# control_driver.net
KiCad netlist of a schematic drawn in EAGLE
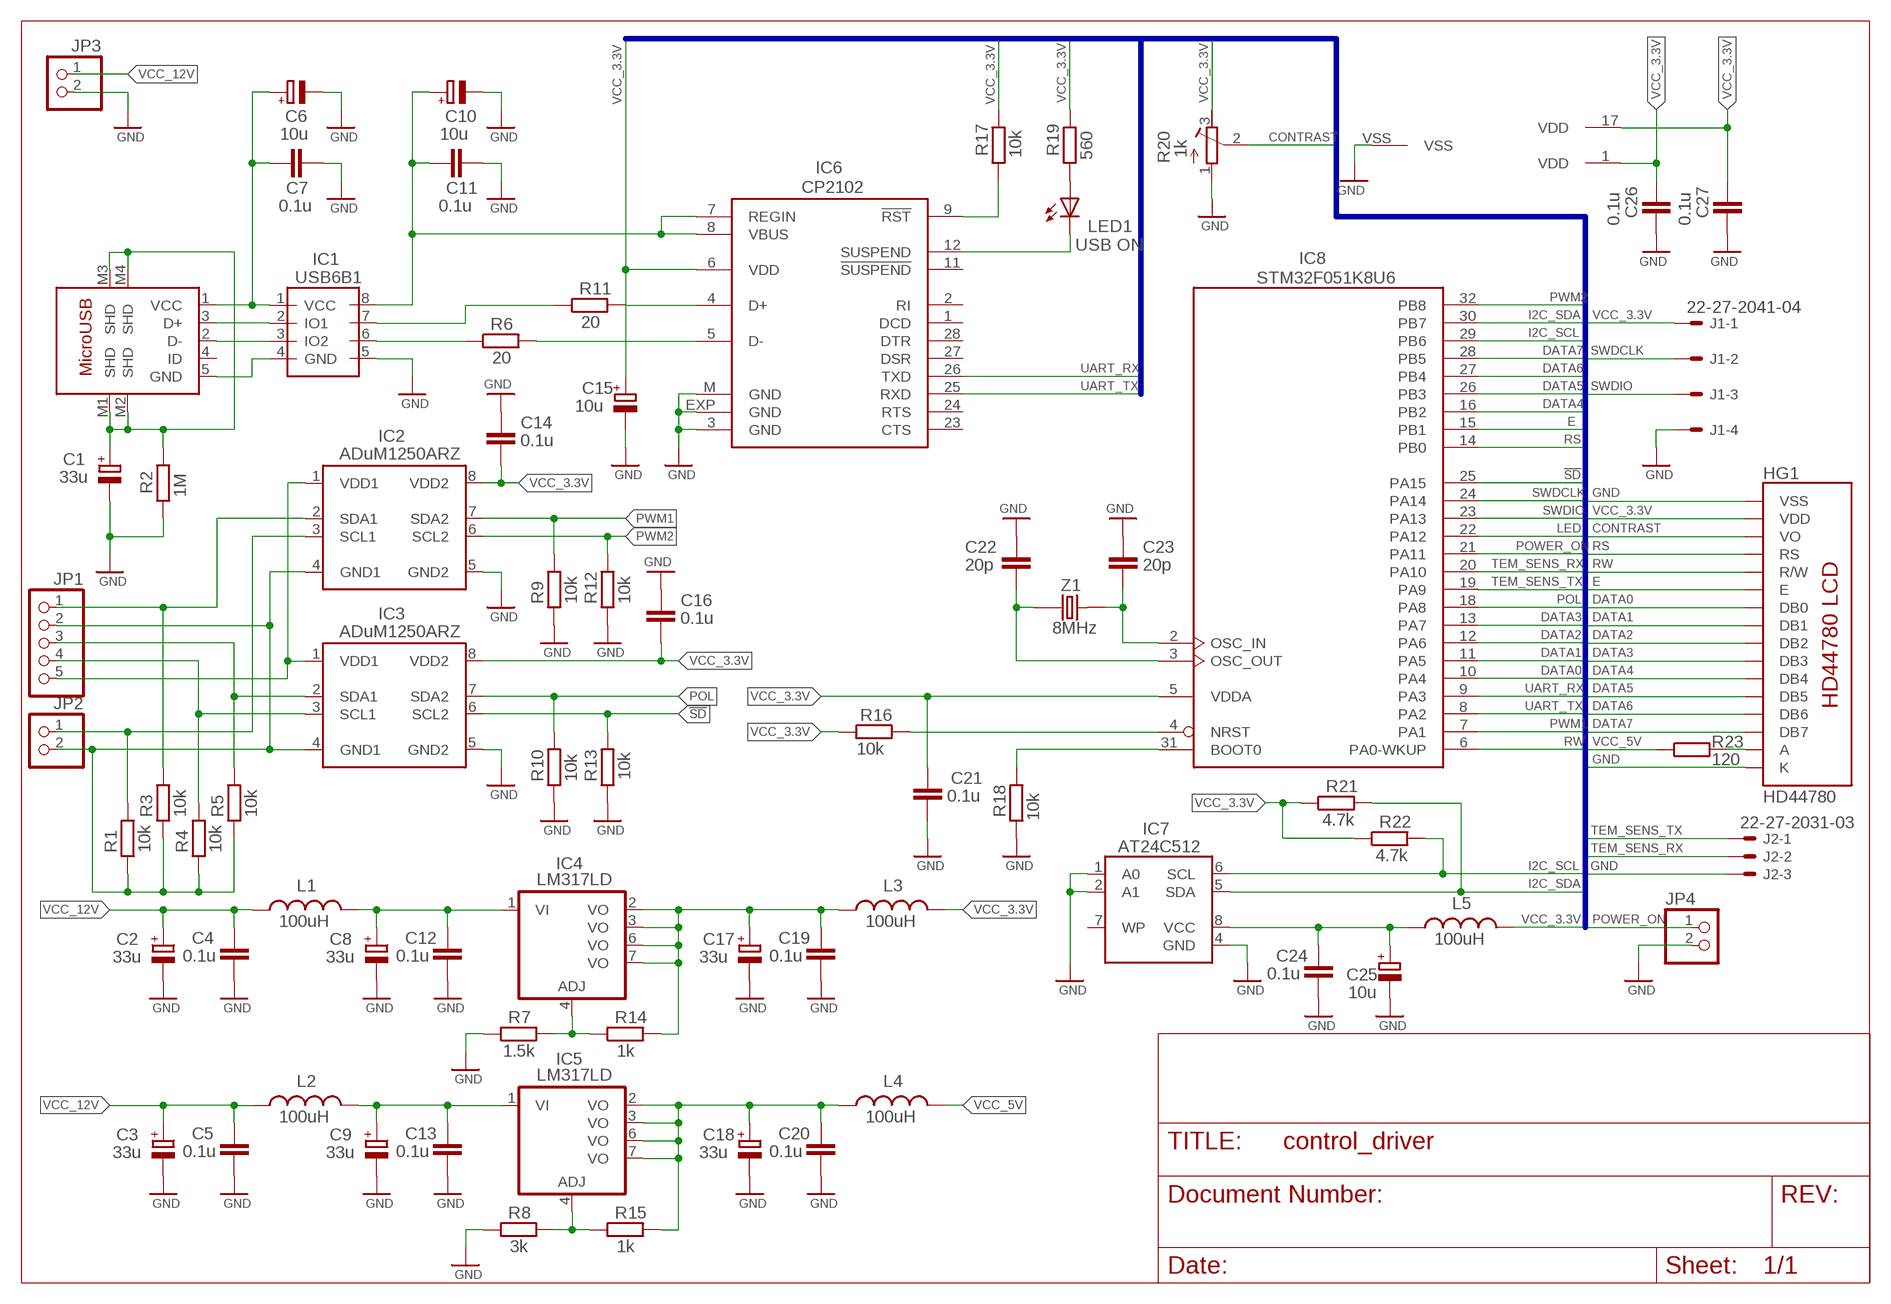
[diagram p0: schematic, sheet 1]

(export (version "E")
  (design (tool "Eeschema 10.0.6"))
  (components
    (comp (ref "C1")
      (value "33u")
      (footprint "eagle-import:SMC_B")
      (libsource (lib "eagle-import") (part "CPOL-EUSMCB"))
    )
    (comp (ref "C2")
      (value "33u")
      (footprint "eagle-import:SMC_C")
      (libsource (lib "eagle-import") (part "CPOL-EUSMCC"))
    )
    (comp (ref "C3")
      (value "33u")
      (footprint "eagle-import:SMC_C")
      (libsource (lib "eagle-import") (part "CPOL-EUSMCC"))
    )
    (comp (ref "C4")
      (value "0.1u")
      (footprint "eagle-import:C0603")
      (libsource (lib "eagle-import") (part "C-EUC0603"))
    )
    (comp (ref "C5")
      (value "0.1u")
      (footprint "eagle-import:C0603")
      (libsource (lib "eagle-import") (part "C-EUC0603"))
    )
    (comp (ref "C6")
      (value "10u")
      (footprint "eagle-import:SMC_A")
      (libsource (lib "eagle-import") (part "CPOL-EUSMCA"))
    )
    (comp (ref "C7")
      (value "0.1u")
      (footprint "eagle-import:C0603")
      (libsource (lib "eagle-import") (part "C-EUC0603"))
    )
    (comp (ref "C8")
      (value "33u")
      (footprint "eagle-import:SMC_C")
      (libsource (lib "eagle-import") (part "CPOL-EUSMCC"))
    )
    (comp (ref "C9")
      (value "33u")
      (footprint "eagle-import:SMC_C")
      (libsource (lib "eagle-import") (part "CPOL-EUSMCC"))
    )
    (comp (ref "C10")
      (value "10u")
      (footprint "eagle-import:SMC_A")
      (libsource (lib "eagle-import") (part "CPOL-EUSMCA"))
    )
    (comp (ref "C11")
      (value "0.1u")
      (footprint "eagle-import:C0603")
      (libsource (lib "eagle-import") (part "C-EUC0603"))
    )
    (comp (ref "C12")
      (value "0.1u")
      (footprint "eagle-import:C0603")
      (libsource (lib "eagle-import") (part "C-EUC0603"))
    )
    (comp (ref "C13")
      (value "0.1u")
      (footprint "eagle-import:C0603")
      (libsource (lib "eagle-import") (part "C-EUC0603"))
    )
    (comp (ref "C14")
      (value "0.1u")
      (footprint "eagle-import:C0603")
      (libsource (lib "eagle-import") (part "C-EUC0603"))
    )
    (comp (ref "C15")
      (value "10u")
      (footprint "eagle-import:SMC_A")
      (libsource (lib "eagle-import") (part "CPOL-EUSMCA"))
    )
    (comp (ref "C16")
      (value "0.1u")
      (footprint "eagle-import:C0603")
      (libsource (lib "eagle-import") (part "C-EUC0603"))
    )
    (comp (ref "C17")
      (value "33u")
      (footprint "eagle-import:SMC_B")
      (libsource (lib "eagle-import") (part "CPOL-EUSMCB"))
    )
    (comp (ref "C18")
      (value "33u")
      (footprint "eagle-import:SMC_B")
      (libsource (lib "eagle-import") (part "CPOL-EUSMCB"))
    )
    (comp (ref "C19")
      (value "0.1u")
      (footprint "eagle-import:C0603")
      (libsource (lib "eagle-import") (part "C-EUC0603"))
    )
    (comp (ref "C20")
      (value "0.1u")
      (footprint "eagle-import:C0603")
      (libsource (lib "eagle-import") (part "C-EUC0603"))
    )
    (comp (ref "C21")
      (value "0.1u")
      (footprint "eagle-import:C0603")
      (libsource (lib "eagle-import") (part "C-EUC0603"))
    )
    (comp (ref "C22")
      (value "20p")
      (footprint "eagle-import:C0603")
      (libsource (lib "eagle-import") (part "C-EUC0603"))
    )
    (comp (ref "C23")
      (value "20p")
      (footprint "eagle-import:C0603")
      (libsource (lib "eagle-import") (part "C-EUC0603"))
    )
    (comp (ref "C24")
      (value "0.1u")
      (footprint "eagle-import:C0603")
      (libsource (lib "eagle-import") (part "C-EUC0603"))
    )
    (comp (ref "C25")
      (value "10u")
      (footprint "eagle-import:SMC_A")
      (libsource (lib "eagle-import") (part "CPOL-EUSMCA"))
    )
    (comp (ref "C26")
      (value "0.1u")
      (footprint "eagle-import:C0603")
      (libsource (lib "eagle-import") (part "C-EUC0603"))
    )
    (comp (ref "C27")
      (value "0.1u")
      (footprint "eagle-import:C0603")
      (libsource (lib "eagle-import") (part "C-EUC0603"))
    )
    (comp (ref "HG1")
      (value "HD44780")
      (footprint "eagle-import:LCD-16X2-4HOLES")
      (libsource (lib "eagle-import") (part "LCD-HD4478016X2-4-HOLES4-HOLES"))
    )
    (comp (ref "IC1")
      (value "USB6B1")
      (footprint "eagle-import:SO08")
      (libsource (lib "eagle-import") (part "USB6B1"))
    )
    (comp (ref "IC2")
      (value "ADuM1250ARZ")
      (footprint "eagle-import:SO8")
      (libsource (lib "eagle-import") (part "ADUM1250"))
    )
    (comp (ref "IC3")
      (value "ADuM1250ARZ")
      (footprint "eagle-import:SO8")
      (libsource (lib "eagle-import") (part "ADUM1250"))
    )
    (comp (ref "IC4")
      (value "LM317LD")
      (footprint "eagle-import:SO08")
      (libsource (lib "eagle-import") (part "LM317LD"))
    )
    (comp (ref "IC5")
      (value "LM317LD")
      (footprint "eagle-import:SO08")
      (libsource (lib "eagle-import") (part "LM317LD"))
    )
    (comp (ref "IC6")
      (value "CP2102")
      (footprint "eagle-import:MLP28")
      (fields (field (name "MF") "FARNELL") (field (name "MPN") "CP2102-GM"))
      (libsource (lib "eagle-import") (part "CP2102"))
    )
    (comp (ref "IC7")
      (value "AT24C512")
      (footprint "eagle-import:SO8")
      (libsource (lib "eagle-import") (part "24C512"))
    )
    (comp (ref "IC8")
      (value "STM32F051K8U6")
      (footprint "eagle-import:UFQFPN32")
      (libsource (lib "eagle-import") (part "STM32F051KU8"))
    )
    (comp (ref "J1")
      (value "22-27-2041-04")
      (footprint "eagle-import:6410-04")
      (libsource (lib "eagle-import") (part "22-?-0427-2041"))
    )
    (comp (ref "J2")
      (value "22-27-2031-03")
      (footprint "eagle-import:6410-03")
      (libsource (lib "eagle-import") (part "22-?-0327-2031"))
    )
    (comp (ref "JP1")
      (value "PINHD-1X55X2MM")
      (footprint "eagle-import:1_05X2MM")
      (libsource (lib "eagle-import") (part "PINHD-1X55X2MM"))
    )
    (comp (ref "JP2")
      (value "PINHD-1X2")
      (footprint "eagle-import:1X02")
      (libsource (lib "eagle-import") (part "PINHD-1X2"))
    )
    (comp (ref "JP3")
      (value "PINHD-1X2")
      (footprint "eagle-import:1X02")
      (libsource (lib "eagle-import") (part "PINHD-1X2"))
    )
    (comp (ref "JP4")
      (value "PINHD-1X2")
      (footprint "eagle-import:1X02")
      (libsource (lib "eagle-import") (part "PINHD-1X2"))
    )
    (comp (ref "L1")
      (value "100uH")
      (footprint "eagle-import:C0603")
      (libsource (lib "eagle-import") (part "L-US"))
    )
    (comp (ref "L2")
      (value "100uH")
      (footprint "eagle-import:C0603")
      (libsource (lib "eagle-import") (part "L-US"))
    )
    (comp (ref "L3")
      (value "100uH")
      (footprint "eagle-import:C0603")
      (libsource (lib "eagle-import") (part "L-US"))
    )
    (comp (ref "L4")
      (value "100uH")
      (footprint "eagle-import:C0603")
      (libsource (lib "eagle-import") (part "L-US"))
    )
    (comp (ref "L5")
      (value "100uH")
      (footprint "eagle-import:C0603")
      (libsource (lib "eagle-import") (part "L-US"))
    )
    (comp (ref "LED1")
      (value "USB ON")
      (footprint "eagle-import:CHIPLED_0805")
      (libsource (lib "eagle-import") (part "LEDCHIPLED_0805"))
    )
    (comp (ref "R1")
      (value "10k")
      (footprint "eagle-import:R0603")
      (libsource (lib "eagle-import") (part "R-EU_R0603"))
    )
    (comp (ref "R2")
      (value "1M")
      (footprint "eagle-import:R0603")
      (libsource (lib "eagle-import") (part "R-EU_R0603"))
    )
    (comp (ref "R3")
      (value "10k")
      (footprint "eagle-import:R0603")
      (libsource (lib "eagle-import") (part "R-EU_R0603"))
    )
    (comp (ref "R4")
      (value "10k")
      (footprint "eagle-import:R0603")
      (libsource (lib "eagle-import") (part "R-EU_R0603"))
    )
    (comp (ref "R5")
      (value "10k")
      (footprint "eagle-import:R0603")
      (libsource (lib "eagle-import") (part "R-EU_R0603"))
    )
    (comp (ref "R6")
      (value "20")
      (footprint "eagle-import:R0603")
      (libsource (lib "eagle-import") (part "R-EU_R0603"))
    )
    (comp (ref "R7")
      (value "1.5k")
      (footprint "eagle-import:R0603")
      (libsource (lib "eagle-import") (part "R-EU_R0603"))
    )
    (comp (ref "R8")
      (value "3k")
      (footprint "eagle-import:R0603")
      (libsource (lib "eagle-import") (part "R-EU_R0603"))
    )
    (comp (ref "R9")
      (value "10k")
      (footprint "eagle-import:R0603")
      (libsource (lib "eagle-import") (part "R-EU_R0603"))
    )
    (comp (ref "R10")
      (value "10k")
      (footprint "eagle-import:R0603")
      (libsource (lib "eagle-import") (part "R-EU_R0603"))
    )
    (comp (ref "R11")
      (value "20")
      (footprint "eagle-import:R0603")
      (libsource (lib "eagle-import") (part "R-EU_R0603"))
    )
    (comp (ref "R12")
      (value "10k")
      (footprint "eagle-import:R0603")
      (libsource (lib "eagle-import") (part "R-EU_R0603"))
    )
    (comp (ref "R13")
      (value "10k")
      (footprint "eagle-import:R0603")
      (libsource (lib "eagle-import") (part "R-EU_R0603"))
    )
    (comp (ref "R14")
      (value "1k")
      (footprint "eagle-import:R0603")
      (libsource (lib "eagle-import") (part "R-EU_R0603"))
    )
    (comp (ref "R15")
      (value "1k")
      (footprint "eagle-import:R0603")
      (libsource (lib "eagle-import") (part "R-EU_R0603"))
    )
    (comp (ref "R16")
      (value "10k")
      (footprint "eagle-import:R0603")
      (libsource (lib "eagle-import") (part "R-EU_R0603"))
    )
    (comp (ref "R17")
      (value "10k")
      (footprint "eagle-import:R0603")
      (libsource (lib "eagle-import") (part "R-EU_R0603"))
    )
    (comp (ref "R18")
      (value "10k")
      (footprint "eagle-import:R0603")
      (libsource (lib "eagle-import") (part "R-EU_R0603"))
    )
    (comp (ref "R19")
      (value "560")
      (footprint "eagle-import:R0603")
      (libsource (lib "eagle-import") (part "R-EU_R0603"))
    )
    (comp (ref "R20")
      (value "1k")
      (footprint "eagle-import:RTRIM4G_J")
      (libsource (lib "eagle-import") (part "R-TRIMM4G/J"))
    )
    (comp (ref "R21")
      (value "4.7k")
      (footprint "eagle-import:R0603")
      (libsource (lib "eagle-import") (part "R-EU_R0603"))
    )
    (comp (ref "R22")
      (value "4.7k")
      (footprint "eagle-import:R0603")
      (libsource (lib "eagle-import") (part "R-EU_R0603"))
    )
    (comp (ref "R23")
      (value "120")
      (footprint "eagle-import:R0805")
      (libsource (lib "eagle-import") (part "R-EU_R0805"))
    )
    (comp (ref "X1")
      (value "MICRO-USB")
      (footprint "eagle-import:ZX62R-B-5P")
      (libsource (lib "eagle-import") (part "MICRO-USB"))
    )
    (comp (ref "Z1")
      (value "8MHz")
      (footprint "eagle-import:CRYSTAL_5X7")
      (libsource (lib "eagle-import") (part "CRYSTAL_5X7MM"))
    )
  )
  (nets
    (net (code "1") (name "/CONTRAST") (class "Default")
      (node (ref "HG1") (pin "3") (pinfunction "VO_3") (pintype "bidirectional"))
      (node (ref "R20") (pin "2") (pinfunction "S_2") (pintype "passive"))
    )
    (net (code "2") (name "/DATA0") (class "Default")
      (node (ref "HG1") (pin "7") (pinfunction "DB0_7") (pintype "bidirectional"))
      (node (ref "IC8") (pin "10") (pinfunction "PA4_10") (pintype "bidirectional"))
    )
    (net (code "3") (name "/DATA1") (class "Default")
      (node (ref "HG1") (pin "8") (pinfunction "DB1_8") (pintype "bidirectional"))
      (node (ref "IC8") (pin "11") (pinfunction "PA5_11") (pintype "bidirectional"))
    )
    (net (code "4") (name "/DATA2") (class "Default")
      (node (ref "HG1") (pin "9") (pinfunction "DB2_9") (pintype "bidirectional"))
      (node (ref "IC8") (pin "12") (pinfunction "PA6_12") (pintype "bidirectional"))
    )
    (net (code "5") (name "/DATA3") (class "Default")
      (node (ref "HG1") (pin "10") (pinfunction "DB3_10") (pintype "bidirectional"))
      (node (ref "IC8") (pin "13") (pinfunction "PA7_13") (pintype "bidirectional"))
    )
    (net (code "6") (name "/DATA4") (class "Default")
      (node (ref "HG1") (pin "11") (pinfunction "DB4_11") (pintype "bidirectional"))
      (node (ref "IC8") (pin "16") (pinfunction "PB2_16") (pintype "bidirectional"))
    )
    (net (code "7") (name "/DATA5") (class "Default")
      (node (ref "HG1") (pin "12") (pinfunction "DB5_12") (pintype "bidirectional"))
      (node (ref "IC8") (pin "26") (pinfunction "PB3_26") (pintype "bidirectional"))
    )
    (net (code "8") (name "/DATA6") (class "Default")
      (node (ref "HG1") (pin "13") (pinfunction "DB6_13") (pintype "bidirectional"))
      (node (ref "IC8") (pin "27") (pinfunction "PB4_27") (pintype "bidirectional"))
    )
    (net (code "9") (name "/DATA7") (class "Default")
      (node (ref "HG1") (pin "14") (pinfunction "DB7_14") (pintype "bidirectional"))
      (node (ref "IC8") (pin "28") (pinfunction "PB5_28") (pintype "bidirectional"))
    )
    (net (code "10") (name "/E") (class "Default")
      (node (ref "HG1") (pin "6") (pinfunction "E_6") (pintype "input"))
      (node (ref "IC8") (pin "15") (pinfunction "PB1_15") (pintype "bidirectional"))
    )
    (net (code "11") (name "/I2C_SCL") (class "Default")
      (node (ref "IC7") (pin "6") (pinfunction "SCL_6") (pintype "bidirectional"))
      (node (ref "IC8") (pin "29") (pinfunction "PB6_29") (pintype "bidirectional"))
      (node (ref "R22") (pin "2") (pinfunction "2_2") (pintype "passive"))
    )
    (net (code "12") (name "/I2C_SDA") (class "Default")
      (node (ref "IC7") (pin "5") (pinfunction "SDA_5") (pintype "bidirectional"))
      (node (ref "IC8") (pin "30") (pinfunction "PB7_30") (pintype "bidirectional"))
      (node (ref "R21") (pin "2") (pinfunction "2_2") (pintype "passive"))
    )
    (net (code "13") (name "/LED") (class "Default")
      (node (ref "IC8") (pin "22") (pinfunction "PA12_22") (pintype "bidirectional"))
    )
    (net (code "14") (name "/POWER_ON") (class "Default")
      (node (ref "IC8") (pin "21") (pinfunction "PA11_21") (pintype "bidirectional"))
      (node (ref "JP4") (pin "1") (pinfunction "1_1") (pintype "passive"))
    )
    (net (code "15") (name "/RS") (class "Default")
      (node (ref "HG1") (pin "4") (pinfunction "RS_4") (pintype "input"))
      (node (ref "IC8") (pin "14") (pinfunction "PB0_14") (pintype "bidirectional"))
    )
    (net (code "16") (name "/RW") (class "Default")
      (node (ref "HG1") (pin "5") (pinfunction "R/W_5") (pintype "input"))
      (node (ref "IC8") (pin "6") (pinfunction "PA0-WKUP_6") (pintype "bidirectional"))
    )
    (net (code "17") (name "/SWDCLK") (class "Default")
      (node (ref "IC8") (pin "24") (pinfunction "PA14_24") (pintype "bidirectional"))
      (node (ref "J1") (pin "2") (pinfunction "S_2") (pintype "passive"))
    )
    (net (code "18") (name "/SWDIO") (class "Default")
      (node (ref "IC8") (pin "23") (pinfunction "PA13_23") (pintype "bidirectional"))
      (node (ref "J1") (pin "3") (pinfunction "S_3") (pintype "passive"))
    )
    (net (code "19") (name "/TEM_SENS_RX") (class "Default")
      (node (ref "IC8") (pin "20") (pinfunction "PA10_20") (pintype "bidirectional"))
      (node (ref "J2") (pin "2") (pinfunction "S_2") (pintype "passive"))
    )
    (net (code "20") (name "/TEM_SENS_TX") (class "Default")
      (node (ref "IC8") (pin "19") (pinfunction "PA9_19") (pintype "bidirectional"))
      (node (ref "J2") (pin "1") (pinfunction "S_1") (pintype "passive"))
    )
    (net (code "21") (name "/UART_RX") (class "Default")
      (node (ref "IC6") (pin "26") (pinfunction "TXD_26") (pintype "output"))
      (node (ref "IC8") (pin "9") (pinfunction "PA3_9") (pintype "bidirectional"))
    )
    (net (code "22") (name "/UART_TX") (class "Default")
      (node (ref "IC6") (pin "25") (pinfunction "RXD_25") (pintype "input"))
      (node (ref "IC8") (pin "8") (pinfunction "PA2_8") (pintype "bidirectional"))
    )
    (net (code "23") (name "/~{SD}") (class "Default")
      (node (ref "IC3") (pin "6") (pinfunction "SCL2_6") (pintype "bidirectional"))
      (node (ref "IC8") (pin "25") (pinfunction "PA15_25") (pintype "bidirectional"))
      (node (ref "R13") (pin "2") (pinfunction "2_2") (pintype "passive"))
    )
    (net (code "24") (name "GND") (class "Default")
      (node (ref "C1") (pin "-") (pinfunction "-_-") (pintype "passive"))
      (node (ref "C10") (pin "-") (pinfunction "-_-") (pintype "passive"))
      (node (ref "C11") (pin "2") (pinfunction "2_2") (pintype "passive"))
      (node (ref "C12") (pin "1") (pinfunction "1_1") (pintype "passive"))
      (node (ref "C13") (pin "1") (pinfunction "1_1") (pintype "passive"))
      (node (ref "C14") (pin "2") (pinfunction "2_2") (pintype "passive"))
      (node (ref "C15") (pin "-") (pinfunction "-_-") (pintype "passive"))
      (node (ref "C16") (pin "2") (pinfunction "2_2") (pintype "passive"))
      (node (ref "C17") (pin "-") (pinfunction "-_-") (pintype "passive"))
      (node (ref "C18") (pin "-") (pinfunction "-_-") (pintype "passive"))
      (node (ref "C19") (pin "1") (pinfunction "1_1") (pintype "passive"))
      (node (ref "C2") (pin "-") (pinfunction "-_-") (pintype "passive"))
      (node (ref "C20") (pin "1") (pinfunction "1_1") (pintype "passive"))
      (node (ref "C21") (pin "1") (pinfunction "1_1") (pintype "passive"))
      (node (ref "C22") (pin "2") (pinfunction "2_2") (pintype "passive"))
      (node (ref "C23") (pin "2") (pinfunction "2_2") (pintype "passive"))
      (node (ref "C24") (pin "1") (pinfunction "1_1") (pintype "passive"))
      (node (ref "C25") (pin "-") (pinfunction "-_-") (pintype "passive"))
      (node (ref "C26") (pin "1") (pinfunction "1_1") (pintype "passive"))
      (node (ref "C27") (pin "1") (pinfunction "1_1") (pintype "passive"))
      (node (ref "C3") (pin "-") (pinfunction "-_-") (pintype "passive"))
      (node (ref "C4") (pin "1") (pinfunction "1_1") (pintype "passive"))
      (node (ref "C5") (pin "1") (pinfunction "1_1") (pintype "passive"))
      (node (ref "C6") (pin "-") (pinfunction "-_-") (pintype "passive"))
      (node (ref "C7") (pin "2") (pinfunction "2_2") (pintype "passive"))
      (node (ref "C8") (pin "-") (pinfunction "-_-") (pintype "passive"))
      (node (ref "C9") (pin "-") (pinfunction "-_-") (pintype "passive"))
      (node (ref "HG1") (pin "1") (pinfunction "VSS_1") (pintype "power_in"))
      (node (ref "HG1") (pin "16") (pinfunction "K_16") (pintype "power_in"))
      (node (ref "IC1") (pin "5") (pinfunction "GND_5") (pintype "power_in"))
      (node (ref "IC2") (pin "5") (pinfunction "GND2_5") (pintype "power_in"))
      (node (ref "IC3") (pin "5") (pinfunction "GND2_5") (pintype "power_in"))
      (node (ref "IC6") (pin "3") (pinfunction "GND_3") (pintype "power_in"))
      (node (ref "IC6") (pin "EXP") (pinfunction "GND_EXP") (pintype "power_in"))
      (node (ref "IC6") (pin "M") (pinfunction "GND_M") (pintype "power_in"))
      (node (ref "IC7") (pin "1") (pinfunction "A0_1") (pintype "bidirectional"))
      (node (ref "IC7") (pin "2") (pinfunction "A1_2") (pintype "bidirectional"))
      (node (ref "IC7") (pin "4") (pinfunction "GND_4") (pintype "power_in"))
      (node (ref "IC8") (pin "VSS") (pinfunction "VSS_VSS") (pintype "power_in"))
      (node (ref "J1") (pin "4") (pinfunction "S_4") (pintype "passive"))
      (node (ref "J2") (pin "3") (pinfunction "S_3") (pintype "passive"))
      (node (ref "JP3") (pin "2") (pinfunction "2_2") (pintype "passive"))
      (node (ref "JP4") (pin "2") (pinfunction "2_2") (pintype "passive"))
      (node (ref "R10") (pin "1") (pinfunction "1_1") (pintype "passive"))
      (node (ref "R12") (pin "1") (pinfunction "1_1") (pintype "passive"))
      (node (ref "R13") (pin "1") (pinfunction "1_1") (pintype "passive"))
      (node (ref "R18") (pin "1") (pinfunction "1_1") (pintype "passive"))
      (node (ref "R2") (pin "1") (pinfunction "1_1") (pintype "passive"))
      (node (ref "R20") (pin "1") (pinfunction "A_1") (pintype "passive"))
      (node (ref "R7") (pin "1") (pinfunction "1_1") (pintype "passive"))
      (node (ref "R8") (pin "1") (pinfunction "1_1") (pintype "passive"))
      (node (ref "R9") (pin "1") (pinfunction "1_1") (pintype "passive"))
    )
    (net (code "25") (name "Net-(C1-Pad+)") (class "Default")
      (node (ref "C1") (pin "+") (pinfunction "+_+") (pintype "passive"))
      (node (ref "R2") (pin "2") (pinfunction "2_2") (pintype "passive"))
      (node (ref "X1") (pin "M1") (pinfunction "SHD_M1") (pintype "power_in"))
      (node (ref "X1") (pin "M2") (pinfunction "SHD_M2") (pintype "power_in"))
      (node (ref "X1") (pin "M3") (pinfunction "SHD_M3") (pintype "power_in"))
      (node (ref "X1") (pin "M4") (pinfunction "SHD_M4") (pintype "power_in"))
    )
    (net (code "26") (name "Net-(C17-Pad+)") (class "Default")
      (node (ref "C17") (pin "+") (pinfunction "+_+") (pintype "passive"))
      (node (ref "C19") (pin "2") (pinfunction "2_2") (pintype "passive"))
      (node (ref "IC4") (pin "2") (pinfunction "VO_2") (pintype "passive"))
      (node (ref "IC4") (pin "3") (pinfunction "VO_3") (pintype "passive"))
      (node (ref "IC4") (pin "6") (pinfunction "VO_6") (pintype "passive"))
      (node (ref "IC4") (pin "7") (pinfunction "VO_7") (pintype "passive"))
      (node (ref "L3") (pin "1") (pinfunction "1_1") (pintype "passive"))
      (node (ref "R14") (pin "2") (pinfunction "2_2") (pintype "passive"))
    )
    (net (code "27") (name "Net-(C18-Pad+)") (class "Default")
      (node (ref "C18") (pin "+") (pinfunction "+_+") (pintype "passive"))
      (node (ref "C20") (pin "2") (pinfunction "2_2") (pintype "passive"))
      (node (ref "IC5") (pin "2") (pinfunction "VO_2") (pintype "passive"))
      (node (ref "IC5") (pin "3") (pinfunction "VO_3") (pintype "passive"))
      (node (ref "IC5") (pin "6") (pinfunction "VO_6") (pintype "passive"))
      (node (ref "IC5") (pin "7") (pinfunction "VO_7") (pintype "passive"))
      (node (ref "L4") (pin "1") (pinfunction "1_1") (pintype "passive"))
      (node (ref "R15") (pin "2") (pinfunction "2_2") (pintype "passive"))
    )
    (net (code "28") (name "Net-(HG1-A)") (class "Default")
      (node (ref "HG1") (pin "15") (pinfunction "A_15") (pintype "power_in"))
      (node (ref "R23") (pin "2") (pinfunction "2_2") (pintype "passive"))
    )
    (net (code "29") (name "Net-(IC1-IO1-Pad7)") (class "Default")
      (node (ref "IC1") (pin "7") (pinfunction "IO1_7") (pintype "bidirectional"))
      (node (ref "R11") (pin "1") (pinfunction "1_1") (pintype "passive"))
    )
    (net (code "30") (name "Net-(IC1-IO2-Pad6)") (class "Default")
      (node (ref "IC1") (pin "6") (pinfunction "IO2_6") (pintype "bidirectional"))
      (node (ref "R6") (pin "1") (pinfunction "1_1") (pintype "passive"))
    )
    (net (code "31") (name "Net-(IC2-GND1)") (class "Default")
      (node (ref "IC2") (pin "4") (pinfunction "GND1_4") (pintype "power_in"))
      (node (ref "IC3") (pin "4") (pinfunction "GND1_4") (pintype "power_in"))
      (node (ref "JP1") (pin "2") (pinfunction "2_2") (pintype "passive"))
      (node (ref "JP2") (pin "2") (pinfunction "2_2") (pintype "passive"))
      (node (ref "R1") (pin "1") (pinfunction "1_1") (pintype "passive"))
      (node (ref "R3") (pin "1") (pinfunction "1_1") (pintype "passive"))
      (node (ref "R4") (pin "1") (pinfunction "1_1") (pintype "passive"))
      (node (ref "R5") (pin "1") (pinfunction "1_1") (pintype "passive"))
    )
    (net (code "32") (name "Net-(IC2-SCL1)") (class "Default")
      (node (ref "IC2") (pin "3") (pinfunction "SCL1_3") (pintype "bidirectional"))
      (node (ref "JP2") (pin "1") (pinfunction "1_1") (pintype "passive"))
      (node (ref "R1") (pin "2") (pinfunction "2_2") (pintype "passive"))
    )
    (net (code "33") (name "Net-(IC2-SDA1)") (class "Default")
      (node (ref "IC2") (pin "2") (pinfunction "SDA1_2") (pintype "bidirectional"))
      (node (ref "JP1") (pin "1") (pinfunction "1_1") (pintype "passive"))
      (node (ref "R3") (pin "2") (pinfunction "2_2") (pintype "passive"))
    )
    (net (code "34") (name "Net-(IC2-VDD1)") (class "Default")
      (node (ref "IC2") (pin "1") (pinfunction "VDD1_1") (pintype "power_in"))
      (node (ref "IC3") (pin "1") (pinfunction "VDD1_1") (pintype "power_in"))
      (node (ref "JP1") (pin "5") (pinfunction "5_5") (pintype "passive"))
    )
    (net (code "35") (name "Net-(IC3-SCL1)") (class "Default")
      (node (ref "IC3") (pin "3") (pinfunction "SCL1_3") (pintype "bidirectional"))
      (node (ref "JP1") (pin "4") (pinfunction "4_4") (pintype "passive"))
      (node (ref "R4") (pin "2") (pinfunction "2_2") (pintype "passive"))
    )
    (net (code "36") (name "Net-(IC3-SDA1)") (class "Default")
      (node (ref "IC3") (pin "2") (pinfunction "SDA1_2") (pintype "bidirectional"))
      (node (ref "JP1") (pin "3") (pinfunction "3_3") (pintype "passive"))
      (node (ref "R5") (pin "2") (pinfunction "2_2") (pintype "passive"))
    )
    (net (code "37") (name "Net-(IC4-ADJ)") (class "Default")
      (node (ref "IC4") (pin "4") (pinfunction "ADJ_4") (pintype "input"))
      (node (ref "R14") (pin "1") (pinfunction "1_1") (pintype "passive"))
      (node (ref "R7") (pin "2") (pinfunction "2_2") (pintype "passive"))
    )
    (net (code "38") (name "Net-(IC4-VI)") (class "Default")
      (node (ref "C12") (pin "2") (pinfunction "2_2") (pintype "passive"))
      (node (ref "C8") (pin "+") (pinfunction "+_+") (pintype "passive"))
      (node (ref "IC4") (pin "1") (pinfunction "VI_1") (pintype "input"))
      (node (ref "L1") (pin "2") (pinfunction "2_2") (pintype "passive"))
    )
    (net (code "39") (name "Net-(IC5-ADJ)") (class "Default")
      (node (ref "IC5") (pin "4") (pinfunction "ADJ_4") (pintype "input"))
      (node (ref "R15") (pin "1") (pinfunction "1_1") (pintype "passive"))
      (node (ref "R8") (pin "2") (pinfunction "2_2") (pintype "passive"))
    )
    (net (code "40") (name "Net-(IC5-VI)") (class "Default")
      (node (ref "C13") (pin "2") (pinfunction "2_2") (pintype "passive"))
      (node (ref "C9") (pin "+") (pinfunction "+_+") (pintype "passive"))
      (node (ref "IC5") (pin "1") (pinfunction "VI_1") (pintype "input"))
      (node (ref "L2") (pin "2") (pinfunction "2_2") (pintype "passive"))
    )
    (net (code "41") (name "Net-(IC6-D+)") (class "Default")
      (node (ref "IC6") (pin "4") (pinfunction "D+_4") (pintype "bidirectional"))
      (node (ref "R11") (pin "2") (pinfunction "2_2") (pintype "passive"))
    )
    (net (code "42") (name "Net-(IC6-D-)") (class "Default")
      (node (ref "IC6") (pin "5") (pinfunction "D-_5") (pintype "bidirectional"))
      (node (ref "R6") (pin "2") (pinfunction "2_2") (pintype "passive"))
    )
    (net (code "43") (name "Net-(IC6-REGIN)") (class "Default")
      (node (ref "C10") (pin "+") (pinfunction "+_+") (pintype "passive"))
      (node (ref "C11") (pin "1") (pinfunction "1_1") (pintype "passive"))
      (node (ref "IC1") (pin "8") (pinfunction "VCC_8") (pintype "power_in"))
      (node (ref "IC6") (pin "7") (pinfunction "REGIN_7") (pintype "passive"))
      (node (ref "IC6") (pin "8") (pinfunction "VBUS_8") (pintype "input"))
    )
    (net (code "44") (name "Net-(IC6-SUSPEND)") (class "Default")
      (node (ref "IC6") (pin "12") (pinfunction "SUSPEND_12") (pintype "output"))
      (node (ref "LED1") (pin "C") (pinfunction "C_C") (pintype "passive"))
    )
    (net (code "45") (name "Net-(IC6-~{RST})") (class "Default")
      (node (ref "IC6") (pin "9") (pinfunction "~{RST}_9") (pintype "bidirectional"))
      (node (ref "R17") (pin "1") (pinfunction "1_1") (pintype "passive"))
    )
    (net (code "46") (name "Net-(IC7-VCC)") (class "Default")
      (node (ref "C24") (pin "2") (pinfunction "2_2") (pintype "passive"))
      (node (ref "C25") (pin "+") (pinfunction "+_+") (pintype "passive"))
      (node (ref "IC7") (pin "8") (pinfunction "VCC_8") (pintype "power_in"))
      (node (ref "L5") (pin "1") (pinfunction "1_1") (pintype "passive"))
    )
    (net (code "47") (name "Net-(IC8A-BOOT0)") (class "Default")
      (node (ref "IC8") (pin "31") (pinfunction "BOOT0_31") (pintype "input"))
      (node (ref "R18") (pin "2") (pinfunction "2_2") (pintype "passive"))
    )
    (net (code "48") (name "Net-(IC8A-NRST)") (class "Default")
      (node (ref "IC8") (pin "4") (pinfunction "NRST_4") (pintype "bidirectional"))
      (node (ref "R16") (pin "2") (pinfunction "2_2") (pintype "passive"))
    )
    (net (code "49") (name "Net-(IC8A-OSC_IN)") (class "Default")
      (node (ref "C23") (pin "1") (pinfunction "1_1") (pintype "passive"))
      (node (ref "IC8") (pin "2") (pinfunction "OSC_IN_2") (pintype "bidirectional"))
      (node (ref "Z1") (pin "P$2") (pinfunction "2_P$2") (pintype "passive"))
    )
    (net (code "50") (name "Net-(IC8A-OSC_OUT)") (class "Default")
      (node (ref "C22") (pin "1") (pinfunction "1_1") (pintype "passive"))
      (node (ref "IC8") (pin "3") (pinfunction "OSC_OUT_3") (pintype "bidirectional"))
      (node (ref "Z1") (pin "P$1") (pinfunction "1_P$1") (pintype "passive"))
    )
    (net (code "51") (name "Net-(LED1-PadA)") (class "Default")
      (node (ref "LED1") (pin "A") (pinfunction "A_A") (pintype "passive"))
      (node (ref "R19") (pin "1") (pinfunction "1_1") (pintype "passive"))
    )
    (net (code "52") (name "Net-(X1-D+)") (class "Default")
      (node (ref "IC1") (pin "2") (pinfunction "IO1_2") (pintype "bidirectional"))
      (node (ref "X1") (pin "3") (pinfunction "D+_3") (pintype "bidirectional"))
    )
    (net (code "53") (name "Net-(X1-D-)") (class "Default")
      (node (ref "IC1") (pin "3") (pinfunction "IO2_3") (pintype "bidirectional"))
      (node (ref "X1") (pin "2") (pinfunction "D-_2") (pintype "bidirectional"))
    )
    (net (code "54") (name "Net-(X1-GND)") (class "Default")
      (node (ref "IC1") (pin "4") (pinfunction "GND_4") (pintype "power_in"))
      (node (ref "X1") (pin "5") (pinfunction "GND_5") (pintype "power_in"))
    )
    (net (code "55") (name "Net-(X1-VCC)") (class "Default")
      (node (ref "C6") (pin "+") (pinfunction "+_+") (pintype "passive"))
      (node (ref "C7") (pin "1") (pinfunction "1_1") (pintype "passive"))
      (node (ref "IC1") (pin "1") (pinfunction "VCC_1") (pintype "power_in"))
      (node (ref "X1") (pin "1") (pinfunction "VCC_1") (pintype "power_in"))
    )
    (net (code "56") (name "POL") (class "Default")
      (node (ref "IC3") (pin "7") (pinfunction "SDA2_7") (pintype "bidirectional"))
      (node (ref "IC8") (pin "18") (pinfunction "PA8_18") (pintype "bidirectional"))
      (node (ref "R10") (pin "2") (pinfunction "2_2") (pintype "passive"))
    )
    (net (code "57") (name "PWM1") (class "Default")
      (node (ref "IC2") (pin "7") (pinfunction "SDA2_7") (pintype "bidirectional"))
      (node (ref "IC8") (pin "7") (pinfunction "PA1_7") (pintype "bidirectional"))
      (node (ref "R9") (pin "2") (pinfunction "2_2") (pintype "passive"))
    )
    (net (code "58") (name "PWM2") (class "Default")
      (node (ref "IC2") (pin "6") (pinfunction "SCL2_6") (pintype "bidirectional"))
      (node (ref "IC8") (pin "32") (pinfunction "PB8_32") (pintype "bidirectional"))
      (node (ref "R12") (pin "2") (pinfunction "2_2") (pintype "passive"))
    )
    (net (code "59") (name "VCC_3.3V") (class "Default")
      (node (ref "C14") (pin "1") (pinfunction "1_1") (pintype "passive"))
      (node (ref "C15") (pin "+") (pinfunction "+_+") (pintype "passive"))
      (node (ref "C16") (pin "1") (pinfunction "1_1") (pintype "passive"))
      (node (ref "C21") (pin "2") (pinfunction "2_2") (pintype "passive"))
      (node (ref "C26") (pin "2") (pinfunction "2_2") (pintype "passive"))
      (node (ref "C27") (pin "2") (pinfunction "2_2") (pintype "passive"))
      (node (ref "HG1") (pin "2") (pinfunction "VDD_2") (pintype "power_in"))
      (node (ref "IC2") (pin "8") (pinfunction "VDD2_8") (pintype "power_in"))
      (node (ref "IC3") (pin "8") (pinfunction "VDD2_8") (pintype "power_in"))
      (node (ref "IC6") (pin "6") (pinfunction "VDD_6") (pintype "power_in"))
      (node (ref "IC8") (pin "1") (pinfunction "VDD_1") (pintype "power_in"))
      (node (ref "IC8") (pin "17") (pinfunction "VDD_17") (pintype "power_in"))
      (node (ref "IC8") (pin "5") (pinfunction "VDDA_5") (pintype "power_in"))
      (node (ref "J1") (pin "1") (pinfunction "S_1") (pintype "passive"))
      (node (ref "L3") (pin "2") (pinfunction "2_2") (pintype "passive"))
      (node (ref "L5") (pin "2") (pinfunction "2_2") (pintype "passive"))
      (node (ref "R16") (pin "1") (pinfunction "1_1") (pintype "passive"))
      (node (ref "R17") (pin "2") (pinfunction "2_2") (pintype "passive"))
      (node (ref "R19") (pin "2") (pinfunction "2_2") (pintype "passive"))
      (node (ref "R20") (pin "3") (pinfunction "E_3") (pintype "passive"))
      (node (ref "R21") (pin "1") (pinfunction "1_1") (pintype "passive"))
      (node (ref "R22") (pin "1") (pinfunction "1_1") (pintype "passive"))
    )
    (net (code "60") (name "VCC_5V") (class "Default")
      (node (ref "L4") (pin "2") (pinfunction "2_2") (pintype "passive"))
      (node (ref "R23") (pin "1") (pinfunction "1_1") (pintype "passive"))
    )
    (net (code "61") (name "VCC_12V") (class "Default")
      (node (ref "C2") (pin "+") (pinfunction "+_+") (pintype "passive"))
      (node (ref "C3") (pin "+") (pinfunction "+_+") (pintype "passive"))
      (node (ref "C4") (pin "2") (pinfunction "2_2") (pintype "passive"))
      (node (ref "C5") (pin "2") (pinfunction "2_2") (pintype "passive"))
      (node (ref "JP3") (pin "1") (pinfunction "1_1") (pintype "passive"))
      (node (ref "L1") (pin "1") (pinfunction "1_1") (pintype "passive"))
      (node (ref "L2") (pin "1") (pinfunction "1_1") (pintype "passive"))
    )
    (net (code "62") (name "unconnected-(IC6-CTS-Pad23)") (class "Default")
      (node (ref "IC6") (pin "23") (pinfunction "CTS_23") (pintype "input"))
    )
    (net (code "63") (name "unconnected-(IC6-DCD-Pad1)") (class "Default")
      (node (ref "IC6") (pin "1") (pinfunction "DCD_1") (pintype "input"))
    )
    (net (code "64") (name "unconnected-(IC6-DSR-Pad27)") (class "Default")
      (node (ref "IC6") (pin "27") (pinfunction "DSR_27") (pintype "input"))
    )
    (net (code "65") (name "unconnected-(IC6-DTR-Pad28)") (class "Default")
      (node (ref "IC6") (pin "28") (pinfunction "DTR_28") (pintype "output"))
    )
    (net (code "66") (name "unconnected-(IC6-RI-Pad2)") (class "Default")
      (node (ref "IC6") (pin "2") (pinfunction "RI_2") (pintype "input"))
    )
    (net (code "67") (name "unconnected-(IC6-RTS-Pad24)") (class "Default")
      (node (ref "IC6") (pin "24") (pinfunction "RTS_24") (pintype "output"))
    )
    (net (code "68") (name "unconnected-(IC6-~{SUSPEND}-Pad11)") (class "Default")
      (node (ref "IC6") (pin "11") (pinfunction "~{SUSPEND}_11") (pintype "output"))
    )
    (net (code "69") (name "unconnected-(IC7-WP-Pad7)") (class "Default")
      (node (ref "IC7") (pin "7") (pinfunction "WP_7") (pintype "bidirectional"))
    )
    (net (code "70") (name "unconnected-(X1-ID-Pad4)") (class "Default")
      (node (ref "X1") (pin "4") (pinfunction "ID_4") (pintype "bidirectional"))
    )
  )
)
